# AMU-S10-V00-AMSContactorInterface.net
KiCad netlist of a schematic drawn in Altium Designer
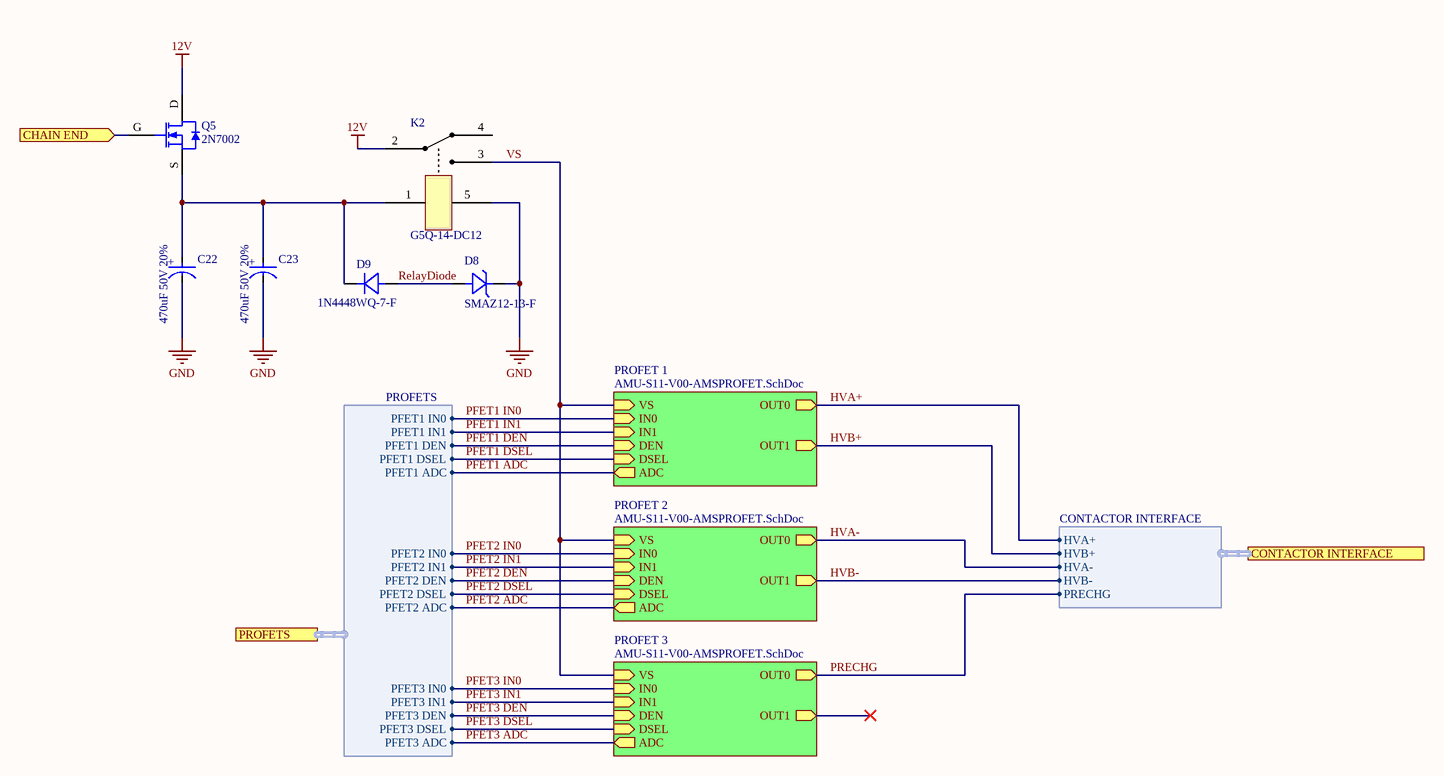
[diagram p0: AMU-S10-V00-AMSContactorInterface.SchDoc]

(export (version "E")
  (design (tool "Eeschema 10.0.6"))
  (components
    (comp (ref "C22")
      (value "470uF 50V 20%")
      (footprint "CAP_ALU_TH")
      (description "470µF 50V Aluminum Electrolytic Capacitors Radial, Can  5000 Hrs @ 105°C")
      (libsource (lib "StandardCapacitors") (part "470uF 50V 20% Alum E-CAP"))
    )
    (comp (ref "C23")
      (value "470uF 50V 20%")
      (footprint "CAP_ALU_TH")
      (description "470µF 50V Aluminum Electrolytic Capacitors Radial, Can  5000 Hrs @ 105°C")
      (libsource (lib "StandardCapacitors") (part "470uF 50V 20% Alum E-CAP"))
    )
    (comp (ref "D8")
      (value "SMAZ12-13-F")
      (footprint "SMA")
      (description "Zener Diode 12V 1W ±5% Surface Mount SMA")
      (fields (field (name "MANUFACTURER") "ON Semiconductor") (field (name "MPN") "MM3Z56VB"))
      (libsource (lib "QUTMS_DiodeLibrary") (part "SMAZ12-13-F"))
    )
    (comp (ref "D9")
      (value "1N4448WQ-7-F")
      (footprint "SMA")
      (description "Diode, SMD, 75V, 5%, 250mA, SOD123")
      (fields
        (field (name "MANUFACTURER") "ON Semiconductor / Fairchild")
        (field (name "MANUFACTURER PART NUMBER") "1N914BWS")
      )
      (libsource (lib "QUTMS_DiodeLibrary") (part "1N4448WQ-7-F"))
    )
    (comp (ref "K2")
      (value "G5Q-14-DC12")
      (footprint "G5Q-14")
      (description "General Purpose Relay SPDT (1 Form C) 12VDC Coil Through Hole, 12V, 16A")
      (libsource (lib "QUTMS_RelayLibrary") (part "G5Q-14-DC12"))
    )
    (comp (ref "Q5")
      (value "2N7002")
      (footprint "SOT23-3")
      (libsource (lib "QUTMS_MOSFETLibrary") (part "2N7002"))
    )
  )
  (nets
    (net (code "4") (name "/CHAIN END") (class "Default")
      (node (ref "Q5") (pin "G") (pinfunction "G_G") (pintype "passive"))
    )
    (net (code "26") (name "/RelayDiode") (class "Default")
      (node (ref "D8") (pin "A") (pinfunction "Anode_A") (pintype "passive"))
      (node (ref "D9") (pin "A") (pinfunction "Anode_A") (pintype "passive"))
    )
    (net (code "27") (name "/VS") (class "Default")
      (node (ref "K2") (pin "3") (pinfunction "3_3") (pintype "passive"))
    )
    (net (code "30") (name "12V") (class "Default")
      (node (ref "K2") (pin "2") (pinfunction "2_2") (pintype "passive"))
      (node (ref "Q5") (pin "D") (pinfunction "D_D") (pintype "passive"))
    )
    (net (code "31") (name "GND") (class "Default")
      (node (ref "C22") (pin "K") (pinfunction "K_K") (pintype "passive"))
      (node (ref "C23") (pin "K") (pinfunction "K_K") (pintype "passive"))
      (node (ref "D8") (pin "K") (pinfunction "Cathode_K") (pintype "passive"))
      (node (ref "K2") (pin "5") (pinfunction "5_5") (pintype "passive"))
    )
    (net (code "32") (name "Net-(D9-Cathode)") (class "Default")
      (node (ref "C22") (pin "A") (pinfunction "A_A") (pintype "passive"))
      (node (ref "C23") (pin "A") (pinfunction "A_A") (pintype "passive"))
      (node (ref "D9") (pin "K") (pinfunction "Cathode_K") (pintype "passive"))
      (node (ref "K2") (pin "1") (pinfunction "1_1") (pintype "passive"))
      (node (ref "Q5") (pin "S") (pinfunction "S_S") (pintype "passive"))
    )
    (net (code "33") (name "unconnected-(K2-Pad4)") (class "Default")
      (node (ref "K2") (pin "4") (pinfunction "4_4") (pintype "passive"))
    )
  )
)
